# trinketm0fader_35mm.net
KiCad netlist of a schematic drawn in EAGLE
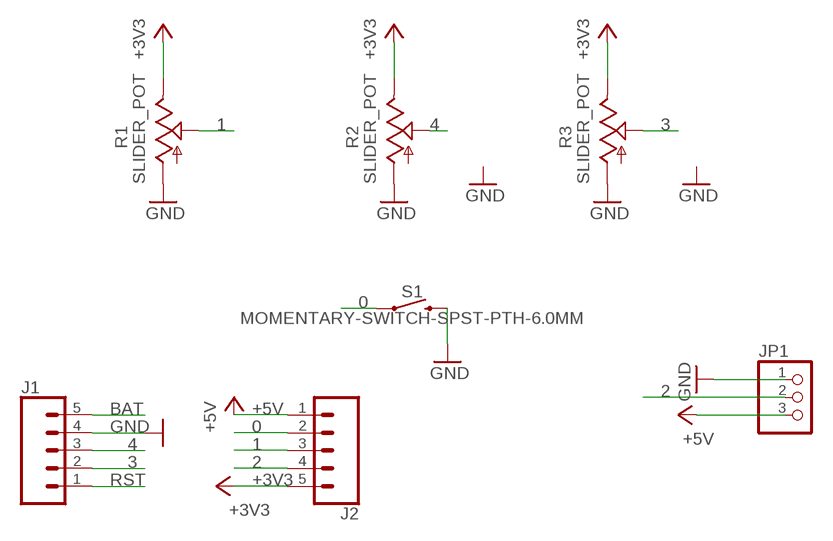
[diagram p0: schematic, sheet 1]

(export (version "E")
  (design (tool "Eeschema 10.0.6"))
  (components
    (comp (ref "J1")
      (value "CONN_05")
      (footprint "eagle-import:1X05")
      (libsource (lib "eagle-import") (part "CONN_05"))
    )
    (comp (ref "J2")
      (value "CONN_05")
      (footprint "eagle-import:1X05")
      (libsource (lib "eagle-import") (part "CONN_05"))
    )
    (comp (ref "JP1")
      (value "PINHD-1X3")
      (footprint "eagle-import:1X03")
      (libsource (lib "eagle-import") (part "PINHD-1X3"))
    )
    (comp (ref "R1")
      (value "SLIDER_POT")
      (footprint "eagle-import:SLIDEPOT_35MM_GUITAR")
      (libsource (lib "eagle-import") (part "SLIDER_POT"))
    )
    (comp (ref "R2")
      (value "SLIDER_POT")
      (footprint "eagle-import:SLIDEPOT_35MM_GUITAR")
      (libsource (lib "eagle-import") (part "SLIDER_POT"))
    )
    (comp (ref "R3")
      (value "SLIDER_POT")
      (footprint "eagle-import:SLIDEPOT_35MM_GUITAR")
      (libsource (lib "eagle-import") (part "SLIDER_POT"))
    )
    (comp (ref "S1")
      (value "MOMENTARY-SWITCH-SPST-PTH-6.0MM")
      (footprint "eagle-import:TACTILE_SWITCH_PTH_6.0MM")
      (libsource (lib "eagle-import") (part "MOMENTARY-SWITCH-SPST-PTH-6.0MM"))
    )
  )
  (nets
    (net (code "1") (name "+3V3") (class "Default")
      (node (ref "J2") (pin "5") (pinfunction "5_5") (pintype "passive"))
      (node (ref "R1") (pin "P$1") (pinfunction "E_P$1") (pintype "passive"))
      (node (ref "R2") (pin "P$1") (pinfunction "E_P$1") (pintype "passive"))
      (node (ref "R3") (pin "P$1") (pinfunction "E_P$1") (pintype "passive"))
    )
    (net (code "2") (name "+5V") (class "Default")
      (node (ref "J2") (pin "1") (pinfunction "1_1") (pintype "passive"))
      (node (ref "JP1") (pin "3") (pinfunction "3_3") (pintype "passive"))
    )
    (net (code "3") (name "/0") (class "Default")
      (node (ref "J2") (pin "2") (pinfunction "2_2") (pintype "passive"))
      (node (ref "S1") (pin "1") (pinfunction "1_1") (pintype "passive"))
    )
    (net (code "4") (name "/1") (class "Default")
      (node (ref "J2") (pin "3") (pinfunction "3_3") (pintype "passive"))
      (node (ref "R1") (pin "P$2") (pinfunction "S_P$2") (pintype "passive"))
    )
    (net (code "5") (name "/2") (class "Default")
      (node (ref "J2") (pin "4") (pinfunction "4_4") (pintype "passive"))
      (node (ref "JP1") (pin "2") (pinfunction "2_2") (pintype "passive"))
    )
    (net (code "6") (name "/3") (class "Default")
      (node (ref "J1") (pin "2") (pinfunction "2_2") (pintype "passive"))
      (node (ref "R3") (pin "P$2") (pinfunction "S_P$2") (pintype "passive"))
    )
    (net (code "7") (name "/4") (class "Default")
      (node (ref "J1") (pin "3") (pinfunction "3_3") (pintype "passive"))
      (node (ref "R2") (pin "P$2") (pinfunction "S_P$2") (pintype "passive"))
    )
    (net (code "8") (name "/BAT") (class "Default")
      (node (ref "J1") (pin "5") (pinfunction "5_5") (pintype "passive"))
    )
    (net (code "9") (name "/RST") (class "Default")
      (node (ref "J1") (pin "1") (pinfunction "1_1") (pintype "passive"))
    )
    (net (code "10") (name "GND") (class "Default")
      (node (ref "J1") (pin "4") (pinfunction "4_4") (pintype "passive"))
      (node (ref "JP1") (pin "1") (pinfunction "1_1") (pintype "passive"))
      (node (ref "R1") (pin "P$4") (pinfunction "A_P$4") (pintype "passive"))
      (node (ref "R2") (pin "P$4") (pinfunction "A_P$4") (pintype "passive"))
      (node (ref "R3") (pin "P$4") (pinfunction "A_P$4") (pintype "passive"))
      (node (ref "S1") (pin "3") (pinfunction "2_3") (pintype "passive"))
    )
  )
)
